# MelansonTech_Boost_PSU_IsolatedShuntAmp.net
KiCad netlist of a schematic drawn in Altium Designer
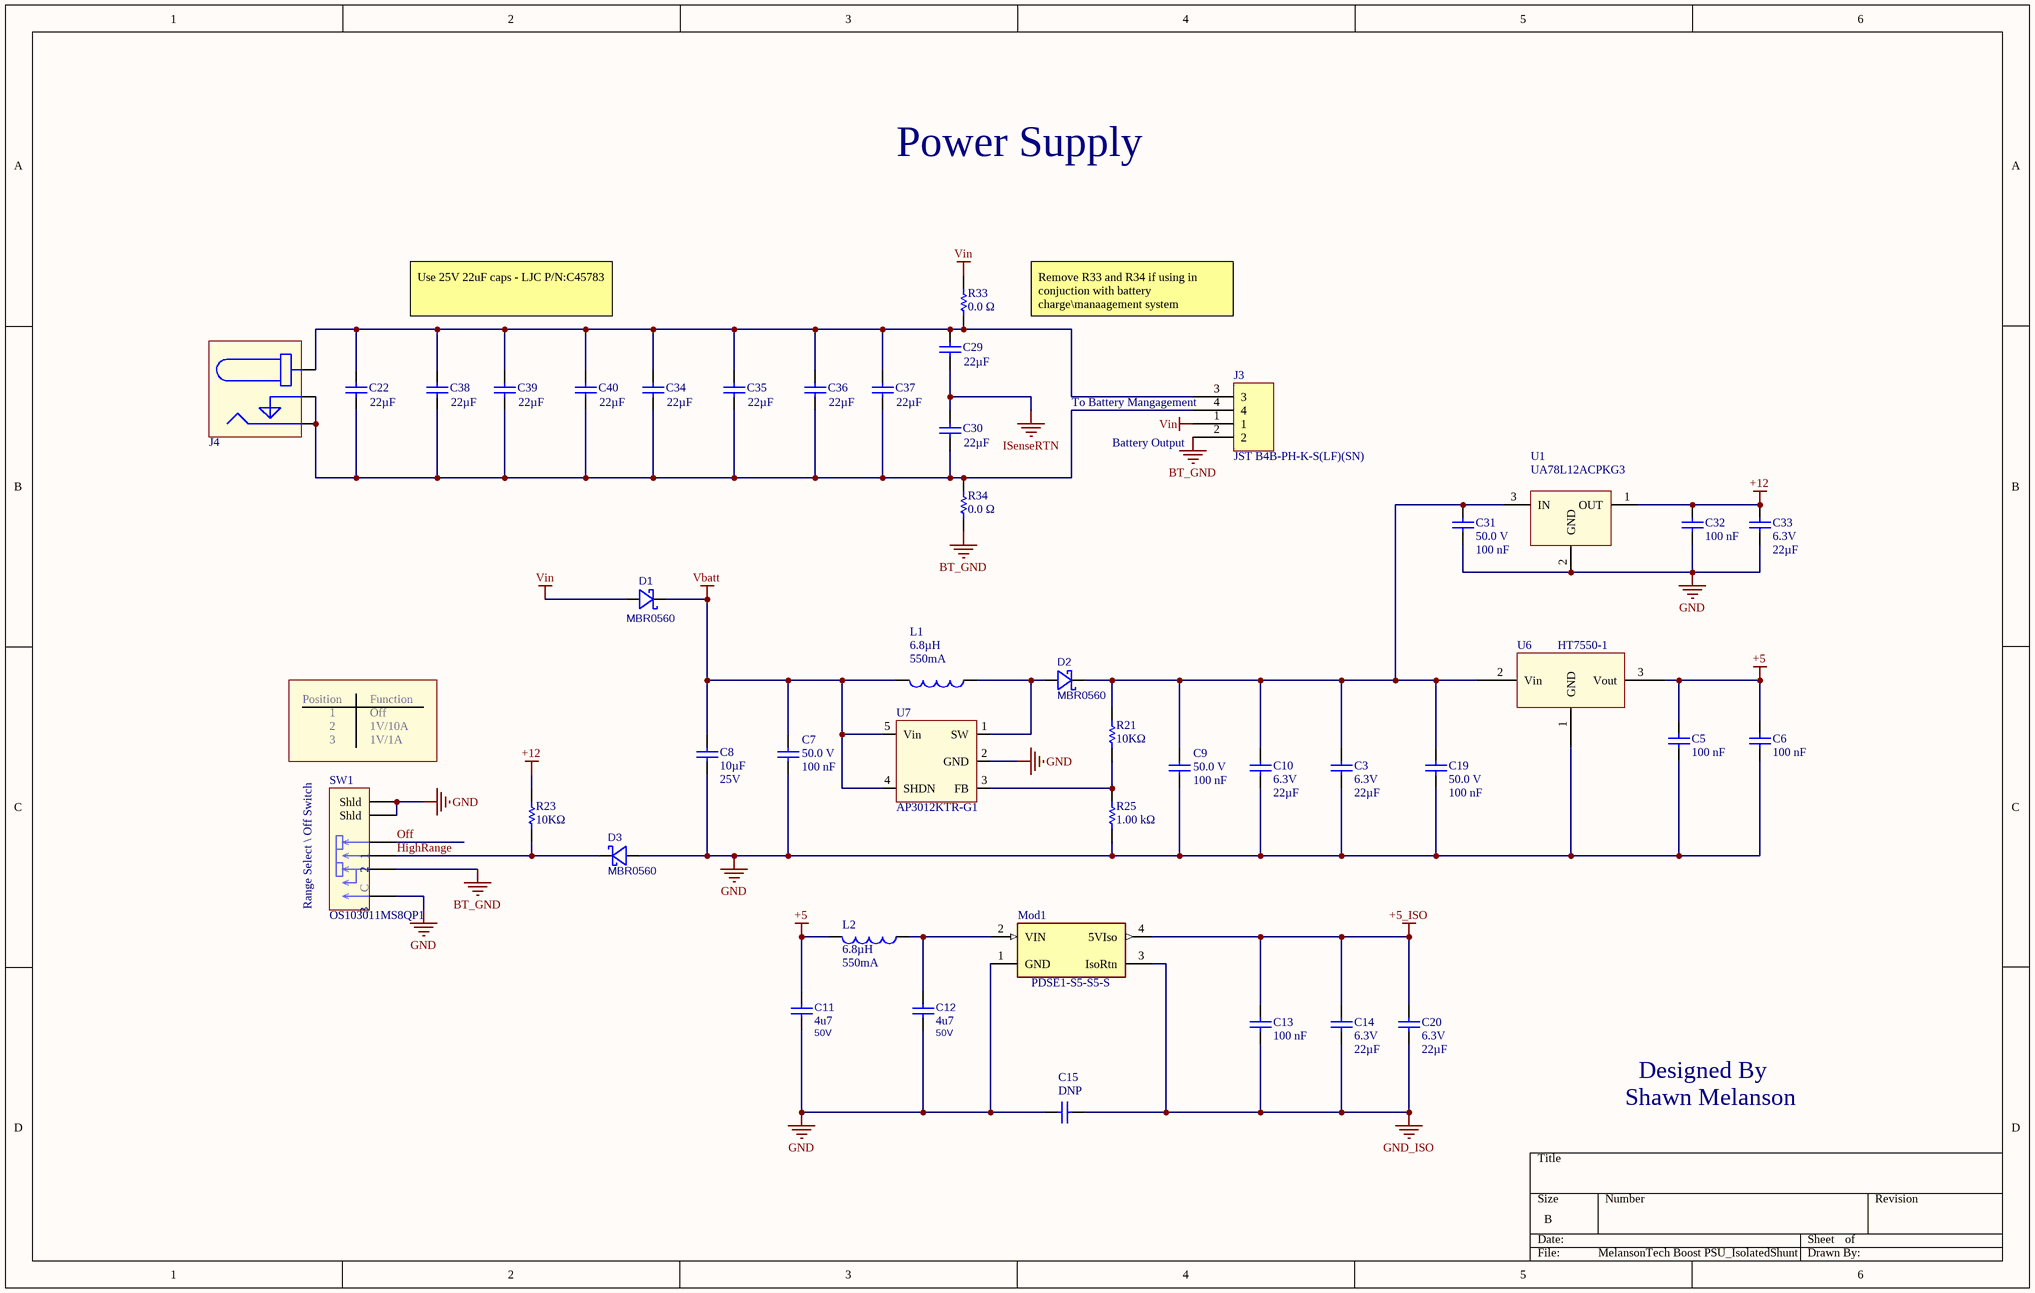
[diagram p0: MelansonTech Boost PSU_IsolatedShuntAmp.SchDoc]

(export (version "E")
  (design (tool "Eeschema 10.0.6"))
  (components
    (comp (ref "C3")
      (value "CL21A226MQQNNNE")
      (footprint "Cap,0805")
      (description "CAP CER 22UF 6.3V X5R 0805")
      (fields
        (field (name "MANUFACTURER") "Samsung Electro-Mechanics")
        (field (name "TOLERANCE") "±20%")
        (field (name "VOLTAGE - RATED") "6.3V")
        (field (name "CAPACITANCE") "22µF")
      )
      (libsource (lib "Master Mar2021") (part "Cap,0805,22uF,6.3V,X5R,±20%,CL21A226MQQNNNE"))
    )
    (comp (ref "C5")
      (value "08055C104JAT2A")
      (footprint "CAP, 0805, HD")
      (description "Capacitor; Ceramic; Cap 0.1 uF; Tol 5%; Vol-Rtg 50 VDC; SMT; 0805; X7R; Tape & Reel")
      (fields (field (name "CAPACITANCE") "100 nF"))
      (libsource (lib "Master Oct28_2018") (part "Cap,0805,100nf,50V,5%,08055C104JAT2A"))
    )
    (comp (ref "C6")
      (value "08055C104JAT2A")
      (footprint "CAP, 0805, HD")
      (description "Capacitor; Ceramic; Cap 0.1 uF; Tol 5%; Vol-Rtg 50 VDC; SMT; 0805; X7R; Tape & Reel")
      (fields (field (name "CAPACITANCE") "100 nF"))
      (libsource (lib "Master Oct28_2018") (part "Cap,0805,100nf,50V,5%,08055C104JAT2A"))
    )
    (comp (ref "C7")
      (value "Cap")
      (footprint "Cap,0805")
      (description "Capacitor; Ceramic; Cap 0.1 uF; Tol 5%; Vol-Rtg 50 VDC; SMT; 0805; X7R; Tape & Reel")
      (fields
        (field (name "MANUFACTURER PART NUMBER") "08055C104JAT2A")
        (field (name "VOLTAGE RATING (DC)") "50.0 V")
        (field (name "CAPACITANCE") "100 nF")
      )
      (libsource (lib "Master JULY2019") (part "Cap,0805,100nf,50V,5%,08055C104JAT2A"))
    )
    (comp (ref "C8")
      (value "C3216X7R1E106K160AB")
      (footprint "Cap, 1206")
      (description "10µF ±10% 25V Ceramic Capacitor X7R 1206 (3216 Metric)")
      (fields
        (field (name "MANUFACTURER") "TDK Corporation")
        (field (name "TOLERANCE") "±10%")
        (field (name "CAPACITANCE") "10µF")
        (field (name "VOLTAGE - RATED") "25V")
      )
      (libsource (lib "Master DEC 2020") (part "CAP,1206,10uF,25V,C3216X7R1E106K160AB"))
    )
    (comp (ref "C9")
      (value "Cap")
      (footprint "Cap,0805")
      (description "Capacitor; Ceramic; Cap 0.1 uF; Tol 5%; Vol-Rtg 50 VDC; SMT; 0805; X7R; Tape & Reel")
      (fields
        (field (name "MANUFACTURER PART NUMBER") "08055C104JAT2A")
        (field (name "VOLTAGE RATING (DC)") "50.0 V")
        (field (name "CAPACITANCE") "100 nF")
      )
      (libsource (lib "Master JULY2019") (part "Cap,0805,100nf,50V,5%,08055C104JAT2A"))
    )
    (comp (ref "C10")
      (value "CL21A226MQQNNNE")
      (footprint "Cap,0805")
      (description "CAP CER 22UF 6.3V X5R 0805")
      (fields
        (field (name "MANUFACTURER") "Samsung Electro-Mechanics")
        (field (name "TOLERANCE") "±20%")
        (field (name "VOLTAGE - RATED") "6.3V")
        (field (name "CAPACITANCE") "22µF")
      )
      (libsource (lib "Master Mar2021") (part "Cap,0805,22uF,6.3V,X5R,±20%,CL21A226MQQNNNE"))
    )
    (comp (ref "C11")
      (value "CL31B475KBHNNNE")
      (footprint "Cap, 1206")
      (description "Cap,SMD,MLCC,4u7,50V,X7R,10%,1206")
      (fields
        (field (name "MANUFACTURER") "Samsung")
        (field (name "TOLERANCE") "10%")
        (field (name "CAPACITANCE") "4u7")
        (field (name "VOLTAGE") "50V")
      )
      (libsource (lib "Master JULY2019") (part "Cap,1206,4.7uF,10%,50V,CL31B475KBHNNNE"))
    )
    (comp (ref "C12")
      (value "CL31B475KBHNNNE")
      (footprint "Cap, 1206")
      (description "Cap,SMD,MLCC,4u7,50V,X7R,10%,1206")
      (fields
        (field (name "MANUFACTURER") "Samsung")
        (field (name "TOLERANCE") "10%")
        (field (name "CAPACITANCE") "4u7")
        (field (name "VOLTAGE") "50V")
      )
      (libsource (lib "Master JULY2019") (part "Cap,1206,4.7uF,10%,50V,CL31B475KBHNNNE"))
    )
    (comp (ref "C13")
      (value "08055C104JAT2A")
      (footprint "CAP, 0805, HD")
      (description "Capacitor; Ceramic; Cap 0.1 uF; Tol 5%; Vol-Rtg 50 VDC; SMT; 0805; X7R; Tape & Reel")
      (fields (field (name "CAPACITANCE") "100 nF"))
      (libsource (lib "Master Oct28_2018") (part "Cap,0805,100nf,50V,5%,08055C104JAT2A"))
    )
    (comp (ref "C14")
      (value "CL21A226MQQNNNE")
      (footprint "Cap,0805")
      (description "CAP CER 22UF 6.3V X5R 0805")
      (fields
        (field (name "MANUFACTURER") "Samsung Electro-Mechanics")
        (field (name "TOLERANCE") "±20%")
        (field (name "VOLTAGE - RATED") "6.3V")
        (field (name "CAPACITANCE") "22µF")
      )
      (libsource (lib "Master Mar2021") (part "Cap,0805,22uF,6.3V,X5R,±20%,CL21A226MQQNNNE"))
    )
    (comp (ref "C15")
      (value "S102K33Y5PP63K5R")
      (footprint "Cap, 5mm Lead Spaceing, 4mm dai")
      (description "CAP CER 1000PF 2KV Y5P RADIAL")
      (fields (field (name "MANUFACTURER") "Vishay BC Components") (field (name "TOLERANCE") "±10%"))
      (libsource (lib "Master JULY2019") (part "Cap,TH,Ceramic,5mm Spacing,1nF,2kV, S102K33Y5PP63K5R"))
    )
    (comp (ref "C19")
      (value "Cap")
      (footprint "Cap,0805")
      (description "Capacitor; Ceramic; Cap 0.1 uF; Tol 5%; Vol-Rtg 50 VDC; SMT; 0805; X7R; Tape & Reel")
      (fields
        (field (name "MANUFACTURER PART NUMBER") "08055C104JAT2A")
        (field (name "VOLTAGE RATING (DC)") "50.0 V")
        (field (name "CAPACITANCE") "100 nF")
      )
      (libsource (lib "Master JULY2019") (part "Cap,0805,100nf,50V,5%,08055C104JAT2A"))
    )
    (comp (ref "C20")
      (value "CL21A226MQQNNNE")
      (footprint "Cap,0805")
      (description "CAP CER 22UF 6.3V X5R 0805")
      (fields
        (field (name "MANUFACTURER") "Samsung Electro-Mechanics")
        (field (name "TOLERANCE") "±20%")
        (field (name "VOLTAGE - RATED") "6.3V")
        (field (name "CAPACITANCE") "22µF")
      )
      (libsource (lib "Master Mar2021") (part "Cap,0805,22uF,6.3V,X5R,±20%,CL21A226MQQNNNE"))
    )
    (comp (ref "C22")
      (value "CL21A226MQQNNNE")
      (footprint "Cap,0805")
      (description "CAP CER 22UF 6.3V X5R 0805")
      (fields
        (field (name "MANUFACTURER") "Samsung Electro-Mechanics")
        (field (name "TOLERANCE") "±20%")
        (field (name "CAPACITANCE") "22µF")
      )
      (libsource (lib "Master Mar2021") (part "Cap,0805,22uF,6.3V,X5R,±20%,CL21A226MQQNNNE"))
    )
    (comp (ref "C29")
      (value "CL21A226MQQNNNE")
      (footprint "Cap,0805")
      (description "CAP CER 22UF 6.3V X5R 0805")
      (fields
        (field (name "MANUFACTURER") "Samsung Electro-Mechanics")
        (field (name "TOLERANCE") "±20%")
        (field (name "CAPACITANCE") "22µF")
      )
      (libsource (lib "Master Mar2021") (part "Cap,0805,22uF,6.3V,X5R,±20%,CL21A226MQQNNNE"))
    )
    (comp (ref "C30")
      (value "CL21A226MQQNNNE")
      (footprint "Cap,0805")
      (description "CAP CER 22UF 6.3V X5R 0805")
      (fields
        (field (name "MANUFACTURER") "Samsung Electro-Mechanics")
        (field (name "TOLERANCE") "±20%")
        (field (name "CAPACITANCE") "22µF")
      )
      (libsource (lib "Master Mar2021") (part "Cap,0805,22uF,6.3V,X5R,±20%,CL21A226MQQNNNE"))
    )
    (comp (ref "C31")
      (value "Cap")
      (footprint "Cap,0805")
      (description "Capacitor; Ceramic; Cap 0.1 uF; Tol 5%; Vol-Rtg 50 VDC; SMT; 0805; X7R; Tape & Reel")
      (fields
        (field (name "MANUFACTURER PART NUMBER") "08055C104JAT2A")
        (field (name "VOLTAGE RATING (DC)") "50.0 V")
        (field (name "CAPACITANCE") "100 nF")
      )
      (libsource (lib "Master JULY2019") (part "Cap,0805,100nf,50V,5%,08055C104JAT2A"))
    )
    (comp (ref "C32")
      (value "08055C104JAT2A")
      (footprint "CAP, 0805, HD")
      (description "Capacitor; Ceramic; Cap 0.1 uF; Tol 5%; Vol-Rtg 50 VDC; SMT; 0805; X7R; Tape & Reel")
      (fields (field (name "CAPACITANCE") "100 nF"))
      (libsource (lib "Master Oct28_2018") (part "Cap,0805,100nf,50V,5%,08055C104JAT2A"))
    )
    (comp (ref "C33")
      (value "CL21A226MQQNNNE")
      (footprint "Cap,0805")
      (description "CAP CER 22UF 6.3V X5R 0805")
      (fields
        (field (name "MANUFACTURER") "Samsung Electro-Mechanics")
        (field (name "TOLERANCE") "±20%")
        (field (name "VOLTAGE - RATED") "6.3V")
        (field (name "CAPACITANCE") "22µF")
      )
      (libsource (lib "Master Mar2021") (part "Cap,0805,22uF,6.3V,X5R,±20%,CL21A226MQQNNNE"))
    )
    (comp (ref "C34")
      (value "CL21A226MQQNNNE")
      (footprint "Cap,0805")
      (description "CAP CER 22UF 6.3V X5R 0805")
      (fields
        (field (name "MANUFACTURER") "Samsung Electro-Mechanics")
        (field (name "TOLERANCE") "±20%")
        (field (name "CAPACITANCE") "22µF")
      )
      (libsource (lib "Master Mar2021") (part "Cap,0805,22uF,6.3V,X5R,±20%,CL21A226MQQNNNE"))
    )
    (comp (ref "C35")
      (value "CL21A226MQQNNNE")
      (footprint "Cap,0805")
      (description "CAP CER 22UF 6.3V X5R 0805")
      (fields
        (field (name "MANUFACTURER") "Samsung Electro-Mechanics")
        (field (name "TOLERANCE") "±20%")
        (field (name "CAPACITANCE") "22µF")
      )
      (libsource (lib "Master Mar2021") (part "Cap,0805,22uF,6.3V,X5R,±20%,CL21A226MQQNNNE"))
    )
    (comp (ref "C36")
      (value "CL21A226MQQNNNE")
      (footprint "Cap,0805")
      (description "CAP CER 22UF 6.3V X5R 0805")
      (fields
        (field (name "MANUFACTURER") "Samsung Electro-Mechanics")
        (field (name "TOLERANCE") "±20%")
        (field (name "CAPACITANCE") "22µF")
      )
      (libsource (lib "Master Mar2021") (part "Cap,0805,22uF,6.3V,X5R,±20%,CL21A226MQQNNNE"))
    )
    (comp (ref "C37")
      (value "CL21A226MQQNNNE")
      (footprint "Cap,0805")
      (description "CAP CER 22UF 6.3V X5R 0805")
      (fields
        (field (name "MANUFACTURER") "Samsung Electro-Mechanics")
        (field (name "TOLERANCE") "±20%")
        (field (name "CAPACITANCE") "22µF")
      )
      (libsource (lib "Master Mar2021") (part "Cap,0805,22uF,6.3V,X5R,±20%,CL21A226MQQNNNE"))
    )
    (comp (ref "C38")
      (value "CL21A226MQQNNNE")
      (footprint "Cap,0805")
      (description "CAP CER 22UF 6.3V X5R 0805")
      (fields
        (field (name "MANUFACTURER") "Samsung Electro-Mechanics")
        (field (name "TOLERANCE") "±20%")
        (field (name "CAPACITANCE") "22µF")
      )
      (libsource (lib "Master Mar2021") (part "Cap,0805,22uF,6.3V,X5R,±20%,CL21A226MQQNNNE"))
    )
    (comp (ref "C39")
      (value "CL21A226MQQNNNE")
      (footprint "Cap,0805")
      (description "CAP CER 22UF 6.3V X5R 0805")
      (fields
        (field (name "MANUFACTURER") "Samsung Electro-Mechanics")
        (field (name "TOLERANCE") "±20%")
        (field (name "CAPACITANCE") "22µF")
      )
      (libsource (lib "Master Mar2021") (part "Cap,0805,22uF,6.3V,X5R,±20%,CL21A226MQQNNNE"))
    )
    (comp (ref "C40")
      (value "CL21A226MQQNNNE")
      (footprint "Cap,0805")
      (description "CAP CER 22UF 6.3V X5R 0805")
      (fields
        (field (name "MANUFACTURER") "Samsung Electro-Mechanics")
        (field (name "TOLERANCE") "±20%")
        (field (name "CAPACITANCE") "22µF")
      )
      (libsource (lib "Master Mar2021") (part "Cap,0805,22uF,6.3V,X5R,±20%,CL21A226MQQNNNE"))
    )
    (comp (ref "D1")
      (value "MBR0560")
      (footprint "SOD123")
      (description "Dio,Sig,Schtky,0.5A,60V,SOD123")
      (fields (field (name "MANUFACTURER") "MCC") (field (name "VOLTAGE") "60V"))
      (libsource (lib "Master DEC 2020") (part "Diode,SOD123,Shottky,60V,0.5A,MBR0560"))
    )
    (comp (ref "D2")
      (value "MBR0560")
      (footprint "SOD123")
      (description "Dio,Sig,Schtky,0.5A,60V,SOD123")
      (fields (field (name "MANUFACTURER") "MCC") (field (name "VOLTAGE") "60V"))
      (libsource (lib "Master DEC 2020") (part "Diode,SOD123,Shottky,60V,0.5A,MBR0560"))
    )
    (comp (ref "D3")
      (value "MBR0560")
      (footprint "SOD123")
      (description "Dio,Sig,Schtky,0.5A,60V,SOD123")
      (fields (field (name "MANUFACTURER") "MCC") (field (name "VOLTAGE") "60V"))
      (libsource (lib "Master DEC 2020") (part "Diode,SOD123,Shottky,60V,0.5A,MBR0560"))
    )
    (comp (ref "J3")
      (value "JST B4B-PH-K-S(LF)(SN)")
      (footprint "Conn, JST, 4 pin, 2mm spacing Right Angle")
      (description "PH Series 4 Position 2 mm Pitch Through Hole Crimp Top Entry Shrouded Header")
      (fields (field (name "MANUFACTURER PART NUMBER") "B4B-PH-K-S(LF)(SN)"))
      (libsource (lib "Master Nov2021") (part "Conntector, though hole, JST, 4pin, 2mm,B4B-PH-K-S(LF)(SN)"))
    )
    (comp (ref "J4")
      (value "PJ-002A")
      (footprint "Connector,Barrel,2.1mm,5.5mm,DC power Jack")
      (description "Power Barrel Connector Jack 2.10mm ID (0.083\"), 5.50mm OD (0.217\") Through Hole, Right Angle")
      (fields (field (name "MANUFACTURER") "CUI Inc."))
      (libsource (lib "Master Nov2021") (part "Connector,Barrel,ID 2.1mm,OD 5.5mm,Power Connect, PJ-002A"))
    )
    (comp (ref "L1")
      (value "MLZ2012N6R8LT000")
      (footprint "Ind, 0805")
      (description "FIXED IND 6.8UH 550MA 250 MOHM")
      (fields
        (field (name "MANUFACTURER") "TDK Corporation")
        (field (name "TOLERANCE") "±20%")
        (field (name "INDUCTANCE") "6.8µH")
        (field (name "CURRENT RATING (AMPS)") "550mA")
      )
      (libsource (lib "Master DEC 2020") (part "Ind,0805,6.8uH,550mA,0.25Ω, MLZ2012N6R8LT000"))
    )
    (comp (ref "L2")
      (value "MLZ2012N6R8LT000")
      (footprint "Ind, 0805")
      (description "FIXED IND 6.8UH 550MA 250 MOHM")
      (fields
        (field (name "MANUFACTURER") "TDK Corporation")
        (field (name "TOLERANCE") "±20%")
        (field (name "INDUCTANCE") "6.8µH")
        (field (name "CURRENT RATING (AMPS)") "550mA")
      )
      (libsource (lib "Master JULY2019") (part "Ind,0805,6.8uH,550mA,0.25Ω, MLZ2012N6R8LT000"))
    )
    (comp (ref "Mod1")
      (value "PDSE1-S5-S5-S")
      (footprint "CONV_PDSE1-S5-S5-S")
      (description "DC-DC ISOLATED, 1 W, 4.5-5.5 VDC")
      (fields (field (name "MANUFACTURER") "CUI Inc."))
      (libsource (lib "Master JULY2019") (part "Mod,PSU,4.5-5.5Vin,5Vout,1W, PDSE1-S5-S5-S"))
    )
    (comp (ref "R21")
      (value "Vishay / Dale CRCW080510K0FKTA")
      (footprint "res, 0805, HD")
      (description "RES SMD 10K OHM 1% 1/8W 0805")
      (fields (field (name "RESISTANCE") "10KΩ"))
      (libsource (lib "Master Mar2021") (part "Res,0805,10.0kΩ,1%,100 ppm,CRCW080510K0FKTA"))
    )
    (comp (ref "R23")
      (value "Vishay / Dale CRCW080510K0FKTA")
      (footprint "res, 0805, HD")
      (description "RES SMD 10K OHM 1% 1/8W 0805")
      (fields (field (name "RESISTANCE") "10KΩ"))
      (libsource (lib "Master JULY2019") (part "Res,0805,10.0kΩ,1%,100 ppm,CRCW080510K0FKTA"))
    )
    (comp (ref "R25")
      (value "Vishay CRCW08051K00JNEA")
      (footprint "res, 0805, HD")
      (description "Res Thick Film 0805 1K Ohm 5% 0.125W(1/8W) ±200ppm/C Molded SMD Automotive Paper T/R")
      (fields
        (field (name "MANUFACTURER PART NUMBER") "CRCW08051K00JNEA")
        (field (name "RESISTANCE") "1.00 kΩ")
      )
      (libsource (lib "Master DEC 2020") (part "Res,0805,1.00 kΩ,5%,200ppm,CRCW08051K00JNEA"))
    )
    (comp (ref "R33")
      (value "CR0805-J/-000ELF")
      (footprint "res, 0805, HD")
      (description "RES SMD 0 OHM JUMPER 1/8W 0805")
      (fields
        (field (name "TOLERANCE") "Jumper")
        (field (name "BASE PART NUMBER") "CR0805")
        (field (name "RESISTANCE") "0.0 Ω")
      )
      (libsource (lib "Master Nov2021") (part "Res,0805,0.0Ω,150V, CR0805-J/-000ELF"))
    )
    (comp (ref "R34")
      (value "CR0805-J/-000ELF")
      (footprint "res, 0805, HD")
      (description "RES SMD 0 OHM JUMPER 1/8W 0805")
      (fields
        (field (name "TOLERANCE") "Jumper")
        (field (name "BASE PART NUMBER") "CR0805")
        (field (name "RESISTANCE") "0.0 Ω")
      )
      (libsource (lib "Master Nov2021") (part "Res,0805,0.0Ω,150V, CR0805-J/-000ELF"))
    )
    (comp (ref "SW1")
      (value "OS103011MS8QP1")
      (footprint "Switch,Slide,.SP3T, OS103011 -Side")
      (description "SWITCH SLIDE SP3T 100MA 12V")
      (fields (field (name "MANUFACTURER") "C&K"))
      (libsource (lib "Master Nov2021") (part "Switch,TH,Slide,SP3T,100MA,12V,OS103011MS8QP1"))
    )
    (comp (ref "U1")
      (value "UA78L12ACPKG3")
      (footprint "SOT89-3")
      (description "IC REG LINEAR 12V 100MA SOT89-3")
      (fields (field (name "MANUFACTURER") "Texas Instruments"))
      (libsource (lib "Master Nov2021") (part "Reg,Linear,Pos,Fixed,12Vout,27Vin,100mA,UA78L12ACPKG3"))
    )
    (comp (ref "U6")
      (value "HT7550-1")
      (footprint "SOT89-3")
      (description "LOW DROPOUT REGULATORS(LDO) POSITIVE FIXED 55MV @ 1MA 30V 5V 150MA SOT-89(SOT-89-3) ROHS")
      (fields
        (field (name "LCSC PART #") "C16106")
        (field (name "MANUFACTURER") "Holtek Semicon")
        (field (name "MFG P/N") "HT7550-1")
      )
      (libsource (lib "Master DEC 2020") (part "Reg,Linear,Fixed,SOT-89-3,30Vin,5Vout,150mA,HT7550-1"))
    )
    (comp (ref "U7")
      (value "AP3012KTR-G1")
      (footprint "SOT23-5")
      (description "IC REG BOOST ADJ 500MA SOT23-5")
      (fields (field (name "MANUFACTURER") "Diodes Incorporated") (field (name "MFG P/N") "AP3012KTR-G1"))
      (libsource (lib "Master DEC 2020") (part "Reg,Switching,Boost,2.6-16Vin,29Vout,0.5A, AP3012KTR-G1"))
    )
  )
  (nets
    (net (code "1") (name "+5") (class "Default")
      (node (ref "C11") (pin "2") (pintype "passive"))
      (node (ref "C5") (pin "2") (pinfunction "2_2") (pintype "passive"))
      (node (ref "C6") (pin "2") (pinfunction "2_2") (pintype "passive"))
      (node (ref "L2") (pin "2") (pinfunction "2_2") (pintype "passive"))
      (node (ref "U6") (pin "3") (pinfunction "Vout_3") (pintype "passive"))
    )
    (net (code "2") (name "+5_ISO") (class "Default")
      (node (ref "C13") (pin "2") (pinfunction "2_2") (pintype "passive"))
      (node (ref "C14") (pin "2") (pinfunction "2_2") (pintype "passive"))
      (node (ref "C20") (pin "2") (pinfunction "2_2") (pintype "passive"))
      (node (ref "Mod1") (pin "4") (pinfunction "5VIso_4") (pintype "output"))
    )
    (net (code "3") (name "+12") (class "Default")
      (node (ref "C32") (pin "2") (pinfunction "2_2") (pintype "passive"))
      (node (ref "C33") (pin "2") (pinfunction "2_2") (pintype "passive"))
      (node (ref "R23") (pin "1") (pinfunction "1_1") (pintype "passive"))
      (node (ref "U1") (pin "1") (pinfunction "OUT_1") (pintype "passive"))
    )
    (net (code "4") (name "/HighRange") (class "Default")
      (node (ref "D3") (pin "1") (pinfunction "C_1") (pintype "passive"))
      (node (ref "R23") (pin "2") (pinfunction "2_2") (pintype "passive"))
      (node (ref "SW1") (pin "3") (pinfunction "3_3") (pintype "passive"))
    )
    (net (code "5") (name "/Off") (class "Default")
      (node (ref "SW1") (pin "4") (pinfunction "4_4") (pintype "passive"))
    )
    (net (code "6") (name "BT_GND") (class "Default")
      (node (ref "J3") (pin "2") (pinfunction "2_2") (pintype "passive"))
      (node (ref "R34") (pin "2") (pinfunction "2_2") (pintype "passive"))
      (node (ref "SW1") (pin "2") (pinfunction "2_2") (pintype "passive"))
    )
    (net (code "7") (name "GND") (class "Default")
      (node (ref "C10") (pin "1") (pinfunction "1_1") (pintype "passive"))
      (node (ref "C11") (pin "1") (pintype "passive"))
      (node (ref "C12") (pin "1") (pintype "passive"))
      (node (ref "C15") (pin "2") (pinfunction "2_2") (pintype "passive"))
      (node (ref "C19") (pin "1") (pinfunction "1_1") (pintype "passive"))
      (node (ref "C3") (pin "1") (pinfunction "1_1") (pintype "passive"))
      (node (ref "C31") (pin "1") (pinfunction "1_1") (pintype "passive"))
      (node (ref "C32") (pin "1") (pinfunction "1_1") (pintype "passive"))
      (node (ref "C33") (pin "1") (pinfunction "1_1") (pintype "passive"))
      (node (ref "C5") (pin "1") (pinfunction "1_1") (pintype "passive"))
      (node (ref "C6") (pin "1") (pinfunction "1_1") (pintype "passive"))
      (node (ref "C7") (pin "1") (pinfunction "1_1") (pintype "passive"))
      (node (ref "C8") (pin "1") (pinfunction "1_1") (pintype "passive"))
      (node (ref "C9") (pin "1") (pinfunction "1_1") (pintype "passive"))
      (node (ref "D3") (pin "2") (pinfunction "A_2") (pintype "passive"))
      (node (ref "Mod1") (pin "1") (pinfunction "GND_1") (pintype "power_in"))
      (node (ref "R25") (pin "2") (pinfunction "2_2") (pintype "passive"))
      (node (ref "SW1") (pin "1") (pinfunction "1_1") (pintype "passive"))
      (node (ref "SW1") (pin "5") (pinfunction "Shld_5") (pintype "passive"))
      (node (ref "SW1") (pin "6") (pinfunction "Shld_6") (pintype "passive"))
      (node (ref "U1") (pin "2") (pinfunction "GND_2") (pintype "passive"))
      (node (ref "U6") (pin "1") (pinfunction "GND_1") (pintype "passive"))
      (node (ref "U7") (pin "2") (pinfunction "GND_2") (pintype "passive"))
    )
    (net (code "8") (name "GND_ISO") (class "Default")
      (node (ref "C13") (pin "1") (pinfunction "1_1") (pintype "passive"))
      (node (ref "C14") (pin "1") (pinfunction "1_1") (pintype "passive"))
      (node (ref "C15") (pin "1") (pinfunction "1_1") (pintype "passive"))
      (node (ref "C20") (pin "1") (pinfunction "1_1") (pintype "passive"))
      (node (ref "Mod1") (pin "3") (pinfunction "IsoRtn_3") (pintype "power_in"))
    )
    (net (code "9") (name "ISenseRTN") (class "Default")
      (node (ref "C29") (pin "1") (pinfunction "1_1") (pintype "passive"))
      (node (ref "C30") (pin "2") (pinfunction "2_2") (pintype "passive"))
    )
    (net (code "10") (name "Net-(C22-Pad1)") (class "Default")
      (node (ref "C22") (pin "1") (pinfunction "1_1") (pintype "passive"))
      (node (ref "C30") (pin "1") (pinfunction "1_1") (pintype "passive"))
      (node (ref "C34") (pin "1") (pinfunction "1_1") (pintype "passive"))
      (node (ref "C35") (pin "1") (pinfunction "1_1") (pintype "passive"))
      (node (ref "C36") (pin "1") (pinfunction "1_1") (pintype "passive"))
      (node (ref "C37") (pin "1") (pinfunction "1_1") (pintype "passive"))
      (node (ref "C38") (pin "1") (pinfunction "1_1") (pintype "passive"))
      (node (ref "C39") (pin "1") (pinfunction "1_1") (pintype "passive"))
      (node (ref "C40") (pin "1") (pinfunction "1_1") (pintype "passive"))
      (node (ref "J3") (pin "4") (pinfunction "4_4") (pintype "passive"))
      (node (ref "J4") (pin "2") (pinfunction "2_2") (pintype "passive"))
      (node (ref "J4") (pin "3") (pinfunction "3_3") (pintype "passive"))
      (node (ref "R34") (pin "1") (pinfunction "1_1") (pintype "passive"))
    )
    (net (code "11") (name "Net-(C22-Pad2)") (class "Default")
      (node (ref "C22") (pin "2") (pinfunction "2_2") (pintype "passive"))
      (node (ref "C29") (pin "2") (pinfunction "2_2") (pintype "passive"))
      (node (ref "C34") (pin "2") (pinfunction "2_2") (pintype "passive"))
      (node (ref "C35") (pin "2") (pinfunction "2_2") (pintype "passive"))
      (node (ref "C36") (pin "2") (pinfunction "2_2") (pintype "passive"))
      (node (ref "C37") (pin "2") (pinfunction "2_2") (pintype "passive"))
      (node (ref "C38") (pin "2") (pinfunction "2_2") (pintype "passive"))
      (node (ref "C39") (pin "2") (pinfunction "2_2") (pintype "passive"))
      (node (ref "C40") (pin "2") (pinfunction "2_2") (pintype "passive"))
      (node (ref "J3") (pin "3") (pinfunction "3_3") (pintype "passive"))
      (node (ref "J4") (pin "1") (pinfunction "1_1") (pintype "passive"))
      (node (ref "R33") (pin "2") (pinfunction "2_2") (pintype "passive"))
    )
    (net (code "12") (name "Net-(D2-A)") (class "Default")
      (node (ref "D2") (pin "2") (pinfunction "A_2") (pintype "passive"))
      (node (ref "L1") (pin "1") (pinfunction "1_1") (pintype "passive"))
      (node (ref "U7") (pin "1") (pinfunction "SW_1") (pintype "passive"))
    )
    (net (code "13") (name "Net-(D2-C)") (class "Default")
      (node (ref "C10") (pin "2") (pinfunction "2_2") (pintype "passive"))
      (node (ref "C19") (pin "2") (pinfunction "2_2") (pintype "passive"))
      (node (ref "C3") (pin "2") (pinfunction "2_2") (pintype "passive"))
      (node (ref "C31") (pin "2") (pinfunction "2_2") (pintype "passive"))
      (node (ref "C9") (pin "2") (pinfunction "2_2") (pintype "passive"))
      (node (ref "D2") (pin "1") (pinfunction "C_1") (pintype "passive"))
      (node (ref "R21") (pin "2") (pinfunction "2_2") (pintype "passive"))
      (node (ref "U1") (pin "3") (pinfunction "IN_3") (pintype "passive"))
      (node (ref "U6") (pin "2") (pinfunction "Vin_2") (pintype "passive"))
    )
    (net (code "14") (name "Net-(Mod1-VIN)") (class "Default")
      (node (ref "C12") (pin "2") (pintype "passive"))
      (node (ref "L2") (pin "1") (pinfunction "1_1") (pintype "passive"))
      (node (ref "Mod1") (pin "2") (pinfunction "VIN_2") (pintype "input"))
    )
    (net (code "15") (name "Net-(U7-FB)") (class "Default")
      (node (ref "R21") (pin "1") (pinfunction "1_1") (pintype "passive"))
      (node (ref "R25") (pin "1") (pinfunction "1_1") (pintype "passive"))
      (node (ref "U7") (pin "3") (pinfunction "FB_3") (pintype "passive"))
    )
    (net (code "16") (name "Vbatt") (class "Default")
      (node (ref "C7") (pin "2") (pinfunction "2_2") (pintype "passive"))
      (node (ref "C8") (pin "2") (pinfunction "2_2") (pintype "passive"))
      (node (ref "D1") (pin "1") (pinfunction "C_1") (pintype "passive"))
      (node (ref "L1") (pin "2") (pinfunction "2_2") (pintype "passive"))
      (node (ref "U7") (pin "4") (pinfunction "SHDN_4") (pintype "passive"))
      (node (ref "U7") (pin "5") (pinfunction "Vin_5") (pintype "passive"))
    )
    (net (code "17") (name "Vin") (class "Default")
      (node (ref "D1") (pin "2") (pinfunction "A_2") (pintype "passive"))
      (node (ref "J3") (pin "1") (pinfunction "1_1") (pintype "passive"))
      (node (ref "R33") (pin "1") (pinfunction "1_1") (pintype "passive"))
    )
  )
)
